# can_tcan1462v.net
KiCad netlist of a schematic drawn in Altium Designer
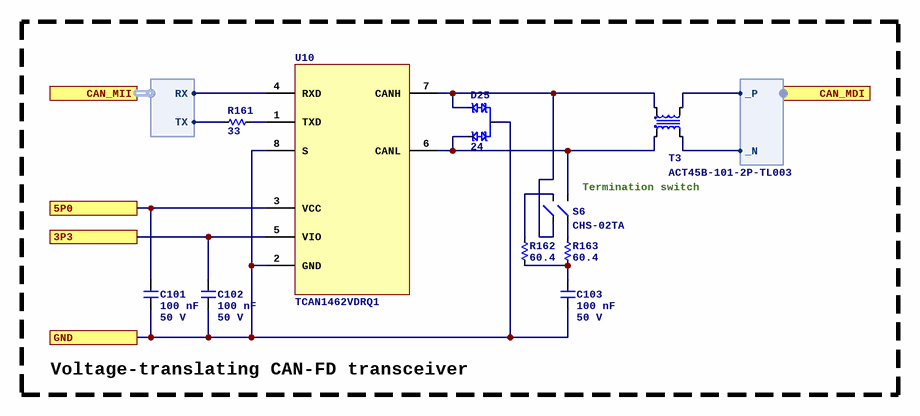
[diagram p0: can_tcan1462v.SchDoc]

(export (version "E")
  (design (tool "Eeschema 10.0.6"))
  (components
    (comp (ref "C101")
      (value "CL05B104KB54PNC")
      (footprint "C0402")
      (fields
        (field (name "CAPACITANCE") "100 nF")
        (field (name "MANUFACTURER") "Samsung Electro-Mechanics")
        (field (name "VOLTAGE RATING") "50 V")
      )
      (libsource (lib "database") (part "__template_cap"))
    )
    (comp (ref "C102")
      (value "CL05B104KB54PNC")
      (footprint "C0402")
      (fields
        (field (name "CAPACITANCE") "100 nF")
        (field (name "MANUFACTURER") "Samsung Electro-Mechanics")
        (field (name "VOLTAGE RATING") "50 V")
      )
      (libsource (lib "database") (part "__template_cap"))
    )
    (comp (ref "C103")
      (value "CL05B104KB54PNC")
      (footprint "C0402")
      (fields
        (field (name "CAPACITANCE") "100 nF")
        (field (name "MANUFACTURER") "Samsung Electro-Mechanics")
        (field (name "VOLTAGE RATING") "50 V")
      )
      (libsource (lib "database") (part "__template_cap"))
    )
    (comp (ref "D25")
      (value "PESD2CAN,215")
      (footprint "3SOT23")
      (description "DIODE ESD CAN SOT-23")
      (fields (field (name "MANUFACTURER") "NXP Semiconductors") (field (name "STANDOFF (V)") "24"))
      (libsource (lib "database") (part "PESD2CAN,215"))
    )
    (comp (ref "R161")
      (value "33")
      (footprint "R0402")
      (fields
        (field (name "TOLERANCE") "1%")
        (field (name "MANUFACTURER PART NUMBER") "0402WGF330JTCE")
        (field (name "MANUFACTURER") "UNI-ROYAL(Uniroyal Elec)")
      )
      (libsource (lib "database") (part "__template_resistor"))
    )
    (comp (ref "R162")
      (value "60.4")
      (footprint "R0402")
      (fields
        (field (name "TOLERANCE") "1%")
        (field (name "MANUFACTURER PART NUMBER") "FRC0402F60R4TS")
        (field (name "MANUFACTURER") "FOJAN")
      )
      (libsource (lib "database") (part "__template_resistor"))
    )
    (comp (ref "R163")
      (value "60.4")
      (footprint "R0402")
      (fields
        (field (name "TOLERANCE") "1%")
        (field (name "MANUFACTURER PART NUMBER") "FRC0402F60R4TS")
        (field (name "MANUFACTURER") "FOJAN")
      )
      (libsource (lib "database") (part "__template_resistor"))
    )
    (comp (ref "S6")
      (value "CHS-02TA")
      (footprint "SWITCH_NIDEC_CHS-02TA")
      (description "DIP Switch, Slide, SPST, Flush, Recessed, 6VDC, 100mA, CHS Series Ž Nidec Components CHS-02TA")
      (fields (field (name "MANUFACTURER") "Nidec Copal"))
      (libsource (lib "database") (part "CHS-02TA"))
    )
    (comp (ref "T3")
      (value "ACT45B-101-2P-TL003")
      (footprint "CHOKE_ACT45B-101-2P-TL003")
      (description "CHOKE COMMON MODE 5000 OHM SMD")
      (fields
        (field (name "MANUFACTURER") "TDK Corporation")
        (field (name "MANUFACTURER PART NUMBER") "ACT45B-101-2P-TL003")
      )
      (libsource (lib "database") (part "__template_transformer"))
    )
    (comp (ref "U10")
      (value "TCAN1462VDRQ1")
      (footprint "8SOIC150")
      (description "Automotive signal improvement CAN FD transceiver with VIO and standby 8-SOIC -40 to 125")
      (fields (field (name "MANUFACTURER") "Texas Instruments"))
      (libsource (lib "database") (part "TCAN1462VDRQ1"))
    )
  )
  (nets
    (net (code "3") (name "/3P3") (class "Default")
      (node (ref "C102") (pin "1") (pintype "passive"))
      (node (ref "U10") (pin "5") (pinfunction "VIO_5") (pintype "passive"))
    )
    (net (code "4") (name "/5P0") (class "Default")
      (node (ref "C101") (pin "1") (pintype "passive"))
      (node (ref "U10") (pin "3") (pinfunction "VCC_3") (pintype "passive"))
    )
    (net (code "5") (name "/GND") (class "Default")
      (node (ref "C101") (pin "2") (pintype "passive"))
      (node (ref "C102") (pin "2") (pintype "passive"))
      (node (ref "C103") (pin "2") (pintype "passive"))
      (node (ref "D25") (pin "3") (pintype "passive"))
      (node (ref "U10") (pin "2") (pinfunction "GND_2") (pintype "passive"))
      (node (ref "U10") (pin "8") (pinfunction "S_8") (pintype "passive"))
    )
    (net (code "6") (name "/RX") (class "Default")
      (node (ref "U10") (pin "4") (pinfunction "RXD_4") (pintype "passive"))
    )
    (net (code "7") (name "/TX") (class "Default") (node (ref "R161") (pin "1") (pintype "passive")))
    (net (code "8") (name "/_N") (class "Default") (node (ref "T3") (pin "3") (pintype "passive")))
    (net (code "9") (name "/_P") (class "Default") (node (ref "T3") (pin "4") (pintype "passive")))
    (net (code "12") (name "Net-(C103-Pad1)") (class "Default")
      (node (ref "C103") (pin "1") (pintype "passive"))
      (node (ref "R162") (pin "2") (pintype "passive"))
      (node (ref "R163") (pin "1") (pintype "passive"))
    )
    (net (code "13") (name "Net-(R162-Pad1)") (class "Default")
      (node (ref "R162") (pin "1") (pintype "passive"))
      (node (ref "S6") (pin "2") (pintype "passive"))
    )
    (net (code "14") (name "Net-(R163-Pad2)") (class "Default")
      (node (ref "R163") (pin "2") (pintype "passive"))
      (node (ref "S6") (pin "3") (pintype "passive"))
    )
    (net (code "15") (name "Net-(U10-CANH)") (class "Default")
      (node (ref "D25") (pin "1") (pintype "passive"))
      (node (ref "S6") (pin "1") (pintype "passive"))
      (node (ref "T3") (pin "1") (pintype "passive"))
      (node (ref "U10") (pin "7") (pinfunction "CANH_7") (pintype "passive"))
    )
    (net (code "16") (name "Net-(U10-CANL)") (class "Default")
      (node (ref "D25") (pin "2") (pintype "passive"))
      (node (ref "S6") (pin "4") (pintype "passive"))
      (node (ref "T3") (pin "2") (pintype "passive"))
      (node (ref "U10") (pin "6") (pinfunction "CANL_6") (pintype "passive"))
    )
    (net (code "17") (name "Net-(U10-TXD)") (class "Default")
      (node (ref "R161") (pin "2") (pintype "passive"))
      (node (ref "U10") (pin "1") (pinfunction "TXD_1") (pintype "passive"))
    )
  )
)
